# Adafruit_Ethernet_FeatherWing.net
KiCad netlist of a schematic drawn in EAGLE
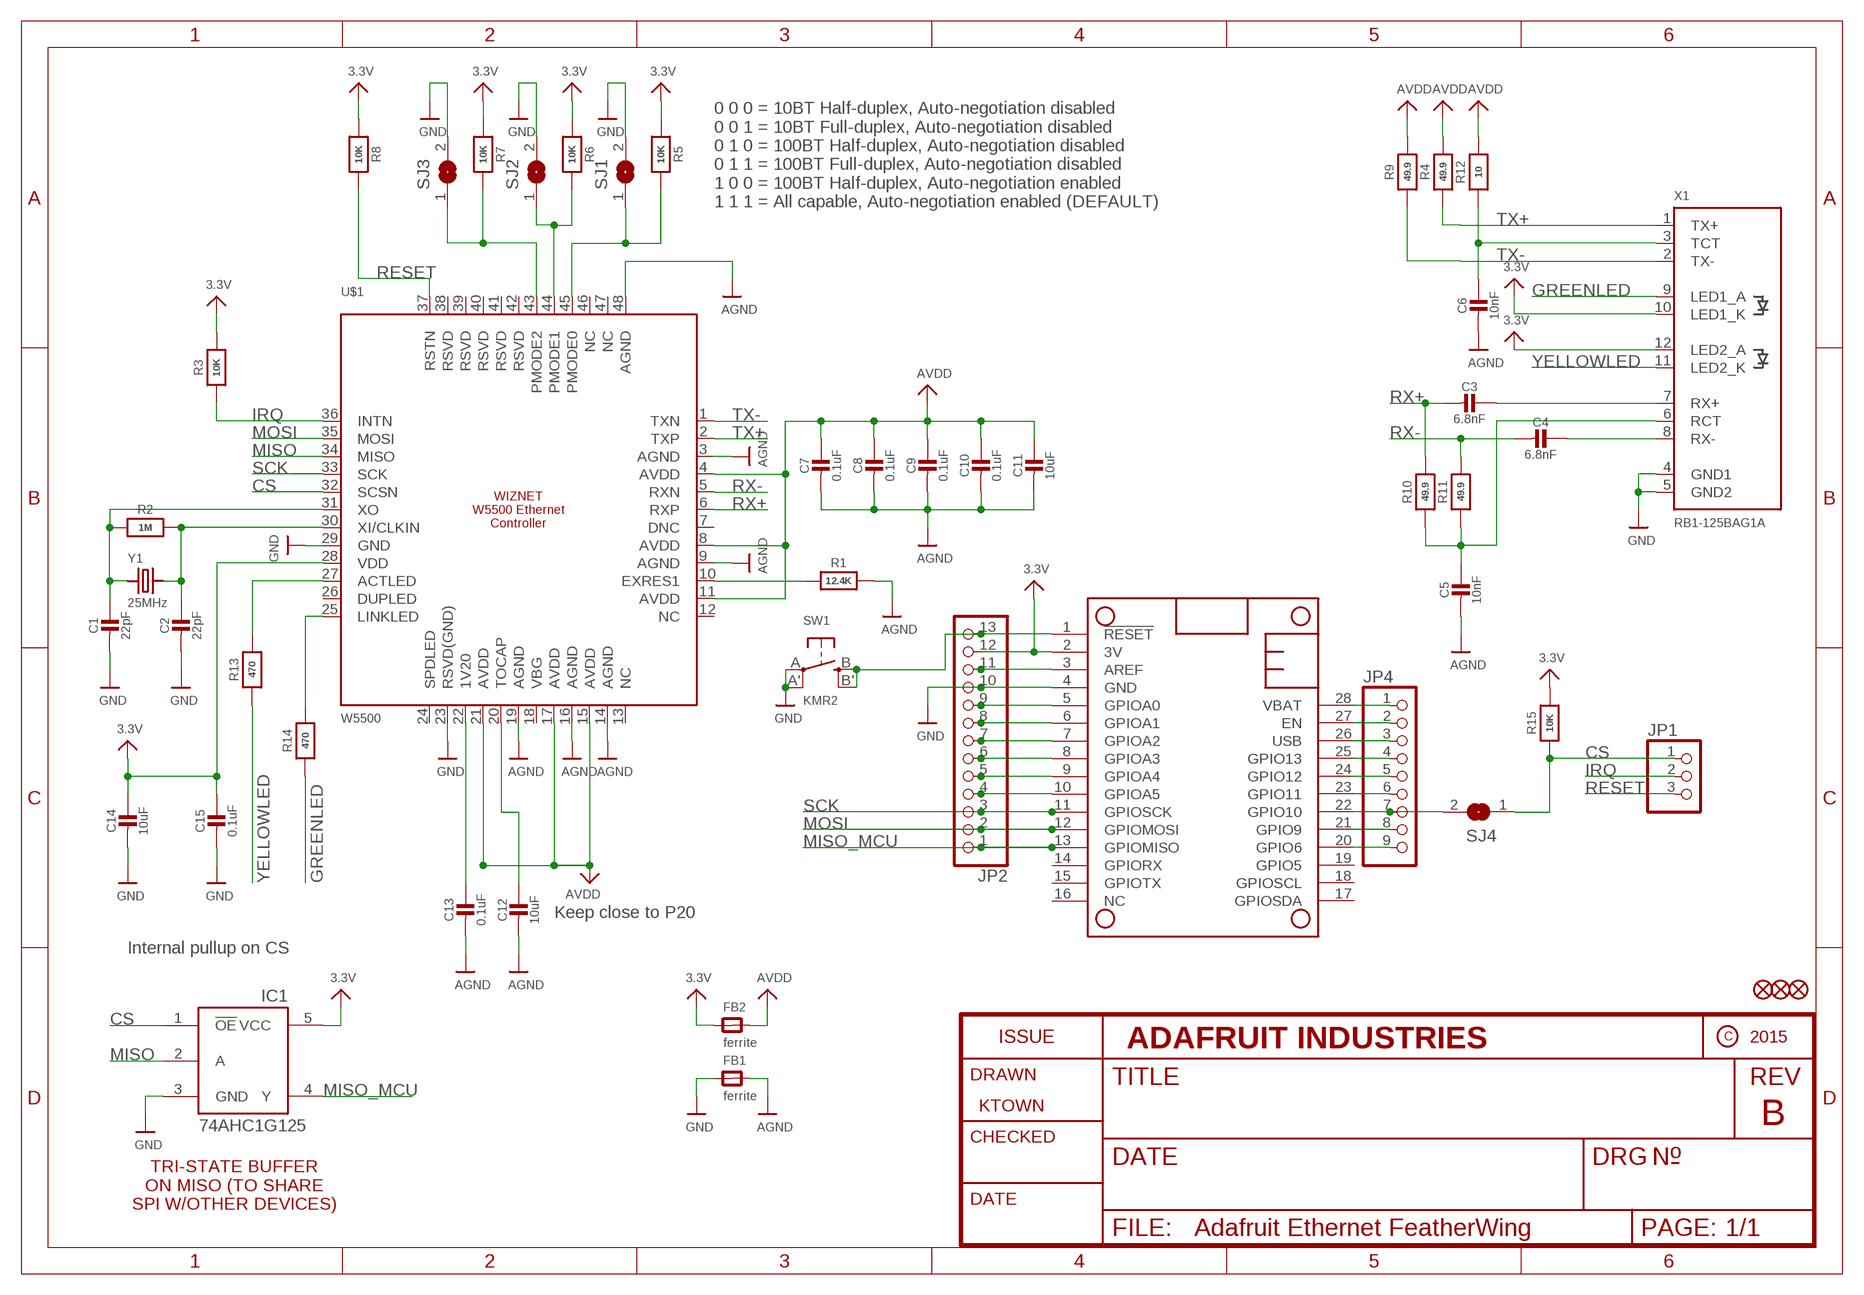
[diagram p0: schematic, sheet 1]

(export (version "E")
  (design (tool "Eeschema 10.0.6"))
  (components
    (comp (ref "C1")
      (value "22pF")
      (footprint "eagle-import:0603-NO")
      (libsource (lib "eagle-import") (part "CAP_CERAMIC0603_NO"))
    )
    (comp (ref "C2")
      (value "22pF")
      (footprint "eagle-import:0603-NO")
      (libsource (lib "eagle-import") (part "CAP_CERAMIC0603_NO"))
    )
    (comp (ref "C3")
      (value "6.8nF")
      (footprint "eagle-import:0603-NO")
      (libsource (lib "eagle-import") (part "CAP_CERAMIC0603_NO"))
    )
    (comp (ref "C4")
      (value "6.8nF")
      (footprint "eagle-import:0603-NO")
      (libsource (lib "eagle-import") (part "CAP_CERAMIC0603_NO"))
    )
    (comp (ref "C5")
      (value "10nF")
      (footprint "eagle-import:0603-NO")
      (libsource (lib "eagle-import") (part "CAP_CERAMIC0603_NO"))
    )
    (comp (ref "C6")
      (value "10nF")
      (footprint "eagle-import:0603-NO")
      (libsource (lib "eagle-import") (part "CAP_CERAMIC0603_NO"))
    )
    (comp (ref "C7")
      (value "0.1uF")
      (footprint "eagle-import:0603-NO")
      (libsource (lib "eagle-import") (part "CAP_CERAMIC0603_NO"))
    )
    (comp (ref "C8")
      (value "0.1uF")
      (footprint "eagle-import:0603-NO")
      (libsource (lib "eagle-import") (part "CAP_CERAMIC0603_NO"))
    )
    (comp (ref "C9")
      (value "0.1uF")
      (footprint "eagle-import:0603-NO")
      (libsource (lib "eagle-import") (part "CAP_CERAMIC0603_NO"))
    )
    (comp (ref "C10")
      (value "0.1uF")
      (footprint "eagle-import:0603-NO")
      (libsource (lib "eagle-import") (part "CAP_CERAMIC0603_NO"))
    )
    (comp (ref "C11")
      (value "10uF")
      (footprint "eagle-import:0805-NO")
      (libsource (lib "eagle-import") (part "CAP_CERAMIC0805-NOOUTLINE"))
    )
    (comp (ref "C12")
      (value "10uF")
      (footprint "eagle-import:0805-NO")
      (libsource (lib "eagle-import") (part "CAP_CERAMIC0805-NOOUTLINE"))
    )
    (comp (ref "C13")
      (value "0.1uF")
      (footprint "eagle-import:0603-NO")
      (libsource (lib "eagle-import") (part "CAP_CERAMIC0603_NO"))
    )
    (comp (ref "C14")
      (value "10uF")
      (footprint "eagle-import:0805-NO")
      (libsource (lib "eagle-import") (part "CAP_CERAMIC0805-NOOUTLINE"))
    )
    (comp (ref "C15")
      (value "0.1uF")
      (footprint "eagle-import:0603-NO")
      (libsource (lib "eagle-import") (part "CAP_CERAMIC0603_NO"))
    )
    (comp (ref "FB1")
      (value "ferrite")
      (footprint "eagle-import:0805-NO")
      (libsource (lib "eagle-import") (part "FERRITE-0805NO"))
    )
    (comp (ref "FB2")
      (value "ferrite")
      (footprint "eagle-import:0805-NO")
      (libsource (lib "eagle-import") (part "FERRITE-0805NO"))
    )
    (comp (ref "FID1")
      (value "FIDUCIAL\"\"")
      (footprint "eagle-import:FIDUCIAL_1MM")
      (libsource (lib "eagle-import") (part "FIDUCIAL{dblquote}{dblquote}"))
    )
    (comp (ref "FID2")
      (value "FIDUCIAL\"\"")
      (footprint "eagle-import:FIDUCIAL_1MM")
      (libsource (lib "eagle-import") (part "FIDUCIAL{dblquote}{dblquote}"))
    )
    (comp (ref "FID3")
      (value "FIDUCIAL\"\"")
      (footprint "eagle-import:FIDUCIAL_1MM")
      (libsource (lib "eagle-import") (part "FIDUCIAL{dblquote}{dblquote}"))
    )
    (comp (ref "IC1")
      (value "74AHC1G125")
      (footprint "eagle-import:SOT23-5L")
      (libsource (lib "eagle-import") (part "74AHC1G125"))
    )
    (comp (ref "JP1")
      (value "HEADER-1X376MIL")
      (footprint "eagle-import:1X03_ROUND_76")
      (libsource (lib "eagle-import") (part "HEADER-1X376MIL"))
    )
    (comp (ref "JP2")
      (value "HEADER-1X13")
      (footprint "eagle-import:1X13_ROUND_70")
      (libsource (lib "eagle-import") (part "HEADER-1X13"))
    )
    (comp (ref "JP4")
      (value "HEADER-1X970MIL")
      (footprint "eagle-import:1X09_ROUND_70")
      (libsource (lib "eagle-import") (part "HEADER-1X970MIL"))
    )
    (comp (ref "MS1")
      (value "FEATHERWING_NODIM")
      (footprint "eagle-import:FEATHERWING_NODIM")
      (libsource (lib "eagle-import") (part "FEATHERWING_NODIM"))
    )
    (comp (ref "R1")
      (value "12.4K")
      (footprint "eagle-import:0603-NO")
      (libsource (lib "eagle-import") (part "RESISTOR_0603_NOOUT"))
    )
    (comp (ref "R2")
      (value "1M")
      (footprint "eagle-import:0603-NO")
      (libsource (lib "eagle-import") (part "RESISTOR_0603_NOOUT"))
    )
    (comp (ref "R3")
      (value "10K")
      (footprint "eagle-import:0603-NO")
      (libsource (lib "eagle-import") (part "RESISTOR_0603_NOOUT"))
    )
    (comp (ref "R4")
      (value "49.9")
      (footprint "eagle-import:0603-NO")
      (libsource (lib "eagle-import") (part "RESISTOR_0603_NOOUT"))
    )
    (comp (ref "R5")
      (value "10K")
      (footprint "eagle-import:0603-NO")
      (libsource (lib "eagle-import") (part "RESISTOR_0603_NOOUT"))
    )
    (comp (ref "R6")
      (value "10K")
      (footprint "eagle-import:0603-NO")
      (libsource (lib "eagle-import") (part "RESISTOR_0603_NOOUT"))
    )
    (comp (ref "R7")
      (value "10K")
      (footprint "eagle-import:0603-NO")
      (libsource (lib "eagle-import") (part "RESISTOR_0603_NOOUT"))
    )
    (comp (ref "R8")
      (value "10K")
      (footprint "eagle-import:0603-NO")
      (libsource (lib "eagle-import") (part "RESISTOR_0603_NOOUT"))
    )
    (comp (ref "R9")
      (value "49.9")
      (footprint "eagle-import:0603-NO")
      (libsource (lib "eagle-import") (part "RESISTOR_0603_NOOUT"))
    )
    (comp (ref "R10")
      (value "49.9")
      (footprint "eagle-import:0603-NO")
      (libsource (lib "eagle-import") (part "RESISTOR_0603_NOOUT"))
    )
    (comp (ref "R11")
      (value "49.9")
      (footprint "eagle-import:0603-NO")
      (libsource (lib "eagle-import") (part "RESISTOR_0603_NOOUT"))
    )
    (comp (ref "R12")
      (value "10")
      (footprint "eagle-import:0603-NO")
      (libsource (lib "eagle-import") (part "RESISTOR_0603_NOOUT"))
    )
    (comp (ref "R13")
      (value "470")
      (footprint "eagle-import:0603-NO")
      (libsource (lib "eagle-import") (part "RESISTOR_0603_NOOUT"))
    )
    (comp (ref "R14")
      (value "470")
      (footprint "eagle-import:0603-NO")
      (libsource (lib "eagle-import") (part "RESISTOR_0603_NOOUT"))
    )
    (comp (ref "R15")
      (value "10K")
      (footprint "eagle-import:0603-NO")
      (libsource (lib "eagle-import") (part "RESISTOR_0603_NOOUT"))
    )
    (comp (ref "SJ1")
      (value "SOLDERJUMPERREFLOW_NOPASTE")
      (footprint "eagle-import:SOLDERJUMPER_REFLOW_NOPASTE")
      (libsource (lib "eagle-import") (part "SOLDERJUMPERREFLOW_NOPASTE"))
    )
    (comp (ref "SJ2")
      (value "SOLDERJUMPERREFLOW_NOPASTE")
      (footprint "eagle-import:SOLDERJUMPER_REFLOW_NOPASTE")
      (libsource (lib "eagle-import") (part "SOLDERJUMPERREFLOW_NOPASTE"))
    )
    (comp (ref "SJ3")
      (value "SOLDERJUMPERREFLOW_NOPASTE")
      (footprint "eagle-import:SOLDERJUMPER_REFLOW_NOPASTE")
      (libsource (lib "eagle-import") (part "SOLDERJUMPERREFLOW_NOPASTE"))
    )
    (comp (ref "SJ4")
      (value "SOLDERJUMPERCLOSED")
      (footprint "eagle-import:SOLDERJUMPER_CLOSEDWIRE")
      (libsource (lib "eagle-import") (part "SOLDERJUMPERCLOSED"))
    )
    (comp (ref "SW1")
      (value "KMR2")
      (footprint "eagle-import:BTN_KMR2_4.6X2.8")
      (libsource (lib "eagle-import") (part "SWITCH_TACT_SMT4.6X2.8"))
    )
    (comp (ref "U$1")
      (value "W5500")
      (footprint "eagle-import:LQFP48")
      (libsource (lib "eagle-import") (part "WIZNET_W5500"))
    )
    (comp (ref "X1")
      (value "RB1-125BAG1A")
      (footprint "eagle-import:RJ45_PULSEJACK")
      (libsource (lib "eagle-import") (part "RJ45J0026D21BNL"))
    )
    (comp (ref "Y1")
      (value "25MHz")
      (footprint "eagle-import:CRYSTAL_3.2X2.5")
      (libsource (lib "eagle-import") (part "CRYSTAL3.2X2.5"))
    )
  )
  (nets
    (net (code "1") (name "/CS") (class "Default")
      (node (ref "IC1") (pin "1") (pinfunction "~{OE}_1") (pintype "input"))
      (node (ref "JP1") (pin "1") (pinfunction "1_1") (pintype "passive"))
      (node (ref "R15") (pin "1") (pinfunction "1_1") (pintype "passive"))
      (node (ref "SJ4") (pin "1") (pinfunction "1_1") (pintype "passive"))
      (node (ref "U$1") (pin "32") (pinfunction "SCSN_32") (pintype "input"))
    )
    (net (code "2") (name "/GREENLED") (class "Default")
      (node (ref "R14") (pin "1") (pinfunction "1_1") (pintype "passive"))
      (node (ref "X1") (pin "9") (pinfunction "LED1_A_9") (pintype "bidirectional"))
    )
    (net (code "3") (name "/IRQ") (class "Default")
      (node (ref "JP1") (pin "2") (pinfunction "2_2") (pintype "passive"))
      (node (ref "R3") (pin "1") (pinfunction "1_1") (pintype "passive"))
      (node (ref "U$1") (pin "36") (pinfunction "INTN_36") (pintype "output"))
    )
    (net (code "4") (name "/MISO") (class "Default")
      (node (ref "IC1") (pin "2") (pinfunction "A_2") (pintype "input"))
      (node (ref "U$1") (pin "34") (pinfunction "MISO_34") (pintype "output"))
    )
    (net (code "5") (name "/MISO_MCU") (class "Default")
      (node (ref "IC1") (pin "4") (pinfunction "Y_4") (pintype "output"))
      (node (ref "JP2") (pin "1") (pinfunction "1_1") (pintype "passive"))
      (node (ref "MS1") (pin "13") (pinfunction "GPIOMISO_13") (pintype "bidirectional"))
    )
    (net (code "6") (name "/MOSI") (class "Default")
      (node (ref "JP2") (pin "2") (pinfunction "2_2") (pintype "passive"))
      (node (ref "MS1") (pin "12") (pinfunction "GPIOMOSI_12") (pintype "bidirectional"))
      (node (ref "U$1") (pin "35") (pinfunction "MOSI_35") (pintype "input"))
    )
    (net (code "7") (name "/RESET") (class "Default")
      (node (ref "JP1") (pin "3") (pinfunction "3_3") (pintype "passive"))
      (node (ref "R8") (pin "2") (pinfunction "2_2") (pintype "passive"))
      (node (ref "U$1") (pin "37") (pinfunction "RSTN_37") (pintype "input"))
    )
    (net (code "8") (name "/RX+") (class "Default")
      (node (ref "C3") (pin "2") (pinfunction "2_2") (pintype "passive"))
      (node (ref "R10") (pin "2") (pinfunction "2_2") (pintype "passive"))
      (node (ref "U$1") (pin "6") (pinfunction "RXP_6") (pintype "input"))
    )
    (net (code "9") (name "/RX-") (class "Default")
      (node (ref "C4") (pin "2") (pinfunction "2_2") (pintype "passive"))
      (node (ref "R11") (pin "2") (pinfunction "2_2") (pintype "passive"))
      (node (ref "U$1") (pin "5") (pinfunction "RXN_5") (pintype "input"))
    )
    (net (code "10") (name "/SCK") (class "Default")
      (node (ref "JP2") (pin "3") (pinfunction "3_3") (pintype "passive"))
      (node (ref "MS1") (pin "11") (pinfunction "GPIOSCK_11") (pintype "bidirectional"))
      (node (ref "U$1") (pin "33") (pinfunction "SCK_33") (pintype "input"))
    )
    (net (code "11") (name "/TX+") (class "Default")
      (node (ref "R4") (pin "1") (pinfunction "1_1") (pintype "passive"))
      (node (ref "U$1") (pin "2") (pinfunction "TXP_2") (pintype "output"))
      (node (ref "X1") (pin "1") (pinfunction "TX+_1") (pintype "bidirectional"))
    )
    (net (code "12") (name "/TX-") (class "Default")
      (node (ref "R9") (pin "1") (pinfunction "1_1") (pintype "passive"))
      (node (ref "U$1") (pin "1") (pinfunction "TXN_1") (pintype "output"))
      (node (ref "X1") (pin "2") (pinfunction "TX-_2") (pintype "bidirectional"))
    )
    (net (code "13") (name "/YELLOWLED") (class "Default")
      (node (ref "R13") (pin "1") (pinfunction "1_1") (pintype "passive"))
      (node (ref "X1") (pin "11") (pinfunction "LED2_K_11") (pintype "bidirectional"))
    )
    (net (code "14") (name "3.3V") (class "Default")
      (node (ref "C14") (pin "1") (pinfunction "1_1") (pintype "passive"))
      (node (ref "C15") (pin "1") (pinfunction "1_1") (pintype "passive"))
      (node (ref "FB2") (pin "1") (pinfunction "P$1_1") (pintype "passive"))
      (node (ref "IC1") (pin "5") (pinfunction "VCC_5") (pintype "power_in"))
      (node (ref "JP2") (pin "12") (pinfunction "12_12") (pintype "passive"))
      (node (ref "MS1") (pin "2") (pinfunction "3V_2") (pintype "power_in"))
      (node (ref "R15") (pin "2") (pinfunction "2_2") (pintype "passive"))
      (node (ref "R3") (pin "2") (pinfunction "2_2") (pintype "passive"))
      (node (ref "R5") (pin "1") (pinfunction "1_1") (pintype "passive"))
      (node (ref "R6") (pin "1") (pinfunction "1_1") (pintype "passive"))
      (node (ref "R7") (pin "1") (pinfunction "1_1") (pintype "passive"))
      (node (ref "R8") (pin "1") (pinfunction "1_1") (pintype "passive"))
      (node (ref "U$1") (pin "28") (pinfunction "VDD_28") (pintype "power_in"))
      (node (ref "X1") (pin "10") (pinfunction "LED1_K_10") (pintype "bidirectional"))
      (node (ref "X1") (pin "12") (pinfunction "LED2_A_12") (pintype "bidirectional"))
    )
    (net (code "15") (name "AGND") (class "Default")
      (node (ref "C10") (pin "2") (pinfunction "2_2") (pintype "passive"))
      (node (ref "C11") (pin "2") (pinfunction "2_2") (pintype "passive"))
      (node (ref "C12") (pin "2") (pinfunction "2_2") (pintype "passive"))
      (node (ref "C13") (pin "2") (pinfunction "2_2") (pintype "passive"))
      (node (ref "C5") (pin "2") (pinfunction "2_2") (pintype "passive"))
      (node (ref "C6") (pin "2") (pinfunction "2_2") (pintype "passive"))
      (node (ref "C7") (pin "2") (pinfunction "2_2") (pintype "passive"))
      (node (ref "C8") (pin "2") (pinfunction "2_2") (pintype "passive"))
      (node (ref "C9") (pin "2") (pinfunction "2_2") (pintype "passive"))
      (node (ref "FB1") (pin "2") (pinfunction "P$2_2") (pintype "passive"))
      (node (ref "R1") (pin "2") (pinfunction "2_2") (pintype "passive"))
      (node (ref "U$1") (pin "14") (pinfunction "AGND_14") (pintype "power_in"))
      (node (ref "U$1") (pin "16") (pinfunction "AGND_16") (pintype "power_in"))
      (node (ref "U$1") (pin "19") (pinfunction "AGND_19") (pintype "power_in"))
      (node (ref "U$1") (pin "3") (pinfunction "AGND_3") (pintype "power_in"))
      (node (ref "U$1") (pin "48") (pinfunction "AGND_48") (pintype "power_in"))
      (node (ref "U$1") (pin "9") (pinfunction "AGND_9") (pintype "power_in"))
    )
    (net (code "16") (name "AVDD") (class "Default")
      (node (ref "C10") (pin "1") (pinfunction "1_1") (pintype "passive"))
      (node (ref "C11") (pin "1") (pinfunction "1_1") (pintype "passive"))
      (node (ref "C7") (pin "1") (pinfunction "1_1") (pintype "passive"))
      (node (ref "C8") (pin "1") (pinfunction "1_1") (pintype "passive"))
      (node (ref "C9") (pin "1") (pinfunction "1_1") (pintype "passive"))
      (node (ref "FB2") (pin "2") (pinfunction "P$2_2") (pintype "passive"))
      (node (ref "R12") (pin "2") (pinfunction "2_2") (pintype "passive"))
      (node (ref "R4") (pin "2") (pinfunction "2_2") (pintype "passive"))
      (node (ref "R9") (pin "2") (pinfunction "2_2") (pintype "passive"))
      (node (ref "U$1") (pin "11") (pinfunction "AVDD_11") (pintype "power_in"))
      (node (ref "U$1") (pin "15") (pinfunction "AVDD_15") (pintype "power_in"))
      (node (ref "U$1") (pin "17") (pinfunction "AVDD_17") (pintype "power_in"))
      (node (ref "U$1") (pin "21") (pinfunction "AVDD_21") (pintype "power_in"))
      (node (ref "U$1") (pin "4") (pinfunction "AVDD_4") (pintype "power_in"))
      (node (ref "U$1") (pin "8") (pinfunction "AVDD_8") (pintype "power_in"))
    )
    (net (code "17") (name "GND") (class "Default")
      (node (ref "C1") (pin "2") (pinfunction "2_2") (pintype "passive"))
      (node (ref "C14") (pin "2") (pinfunction "2_2") (pintype "passive"))
      (node (ref "C15") (pin "2") (pinfunction "2_2") (pintype "passive"))
      (node (ref "C2") (pin "2") (pinfunction "2_2") (pintype "passive"))
      (node (ref "FB1") (pin "1") (pinfunction "P$1_1") (pintype "passive"))
      (node (ref "IC1") (pin "3") (pinfunction "GND_3") (pintype "power_in"))
      (node (ref "JP2") (pin "10") (pinfunction "10_10") (pintype "passive"))
      (node (ref "MS1") (pin "4") (pinfunction "GND_4") (pintype "power_in"))
      (node (ref "SJ1") (pin "2") (pinfunction "2_2") (pintype "passive"))
      (node (ref "SJ2") (pin "2") (pinfunction "2_2") (pintype "passive"))
      (node (ref "SJ3") (pin "2") (pinfunction "2_2") (pintype "passive"))
      (node (ref "SW1") (pin "A") (pinfunction "P_A") (pintype "passive"))
      (node (ref "SW1") (pin "A'") (pinfunction "P1_A'") (pintype "passive"))
      (node (ref "U$1") (pin "23") (pinfunction "RSVD(GND)_23") (pintype "input"))
      (node (ref "U$1") (pin "29") (pinfunction "GND_29") (pintype "power_in"))
      (node (ref "X1") (pin "4") (pinfunction "GND1_4") (pintype "bidirectional"))
      (node (ref "X1") (pin "5") (pinfunction "GND2_5") (pintype "bidirectional"))
    )
    (net (code "18") (name "Net-(MS1-AREF)") (class "Default")
      (node (ref "JP2") (pin "11") (pinfunction "11_11") (pintype "passive"))
      (node (ref "MS1") (pin "3") (pinfunction "AREF_3") (pintype "passive"))
    )
    (net (code "19") (name "Net-(MS1-EN)") (class "Default")
      (node (ref "JP4") (pin "2") (pinfunction "2_2") (pintype "passive"))
      (node (ref "MS1") (pin "27") (pinfunction "EN_27") (pintype "passive"))
    )
    (net (code "20") (name "Net-(MS1-GPIO6)") (class "Default")
      (node (ref "JP4") (pin "9") (pinfunction "9_9") (pintype "passive"))
      (node (ref "MS1") (pin "20") (pinfunction "GPIO6_20") (pintype "bidirectional"))
    )
    (net (code "21") (name "Net-(MS1-GPIO9)") (class "Default")
      (node (ref "JP4") (pin "8") (pinfunction "8_8") (pintype "passive"))
      (node (ref "MS1") (pin "21") (pinfunction "GPIO9_21") (pintype "bidirectional"))
    )
    (net (code "22") (name "Net-(MS1-GPIO10)") (class "Default")
      (node (ref "JP4") (pin "7") (pinfunction "7_7") (pintype "passive"))
      (node (ref "MS1") (pin "22") (pinfunction "GPIO10_22") (pintype "bidirectional"))
      (node (ref "SJ4") (pin "2") (pinfunction "2_2") (pintype "passive"))
    )
    (net (code "23") (name "Net-(MS1-GPIO11)") (class "Default")
      (node (ref "JP4") (pin "6") (pinfunction "6_6") (pintype "passive"))
      (node (ref "MS1") (pin "23") (pinfunction "GPIO11_23") (pintype "bidirectional"))
    )
    (net (code "24") (name "Net-(MS1-GPIO12)") (class "Default")
      (node (ref "JP4") (pin "5") (pinfunction "5_5") (pintype "passive"))
      (node (ref "MS1") (pin "24") (pinfunction "GPIO12_24") (pintype "bidirectional"))
    )
    (net (code "25") (name "Net-(MS1-GPIO13)") (class "Default")
      (node (ref "JP4") (pin "4") (pinfunction "4_4") (pintype "passive"))
      (node (ref "MS1") (pin "25") (pinfunction "GPIO13_25") (pintype "bidirectional"))
    )
    (net (code "26") (name "Net-(MS1-GPIOA0)") (class "Default")
      (node (ref "JP2") (pin "9") (pinfunction "9_9") (pintype "passive"))
      (node (ref "MS1") (pin "5") (pinfunction "GPIOA0_5") (pintype "bidirectional"))
    )
    (net (code "27") (name "Net-(MS1-GPIOA1)") (class "Default")
      (node (ref "JP2") (pin "8") (pinfunction "8_8") (pintype "passive"))
      (node (ref "MS1") (pin "6") (pinfunction "GPIOA1_6") (pintype "bidirectional"))
    )
    (net (code "28") (name "Net-(MS1-GPIOA2)") (class "Default")
      (node (ref "JP2") (pin "7") (pinfunction "7_7") (pintype "passive"))
      (node (ref "MS1") (pin "7") (pinfunction "GPIOA2_7") (pintype "bidirectional"))
    )
    (net (code "29") (name "Net-(MS1-GPIOA3)") (class "Default")
      (node (ref "JP2") (pin "6") (pinfunction "6_6") (pintype "passive"))
      (node (ref "MS1") (pin "8") (pinfunction "GPIOA3_8") (pintype "bidirectional"))
    )
    (net (code "30") (name "Net-(MS1-GPIOA4)") (class "Default")
      (node (ref "JP2") (pin "5") (pinfunction "5_5") (pintype "passive"))
      (node (ref "MS1") (pin "9") (pinfunction "GPIOA4_9") (pintype "bidirectional"))
    )
    (net (code "31") (name "Net-(MS1-GPIOA5)") (class "Default")
      (node (ref "JP2") (pin "4") (pinfunction "4_4") (pintype "passive"))
      (node (ref "MS1") (pin "10") (pinfunction "GPIOA5_10") (pintype "bidirectional"))
    )
    (net (code "32") (name "Net-(MS1-USB)") (class "Default")
      (node (ref "JP4") (pin "3") (pinfunction "3_3") (pintype "passive"))
      (node (ref "MS1") (pin "26") (pinfunction "USB_26") (pintype "power_in"))
    )
    (net (code "33") (name "Net-(MS1-VBAT)") (class "Default")
      (node (ref "JP4") (pin "1") (pinfunction "1_1") (pintype "passive"))
      (node (ref "MS1") (pin "28") (pinfunction "VBAT_28") (pintype "power_in"))
    )
    (net (code "34") (name "Net-(MS1-~{RESET})") (class "Default")
      (node (ref "JP2") (pin "13") (pinfunction "13_13") (pintype "passive"))
      (node (ref "MS1") (pin "1") (pinfunction "~{RESET}_1") (pintype "input"))
      (node (ref "SW1") (pin "B") (pinfunction "S_B") (pintype "passive"))
      (node (ref "SW1") (pin "B'") (pinfunction "S1_B'") (pintype "passive"))
    )
    (net (code "35") (name "Net-(U$1-1V20)") (class "Default")
      (node (ref "C13") (pin "1") (pinfunction "1_1") (pintype "passive"))
      (node (ref "U$1") (pin "22") (pinfunction "1V20_22") (pintype "power_in"))
    )
    (net (code "36") (name "Net-(U$1-ACTLED)") (class "Default")
      (node (ref "R13") (pin "2") (pinfunction "2_2") (pintype "passive"))
      (node (ref "U$1") (pin "27") (pinfunction "ACTLED_27") (pintype "output"))
    )
    (net (code "37") (name "Net-(U$1-EXRES1)") (class "Default")
      (node (ref "R1") (pin "1") (pinfunction "1_1") (pintype "passive"))
      (node (ref "U$1") (pin "10") (pinfunction "EXRES1_10") (pintype "bidirectional"))
    )
    (net (code "38") (name "Net-(U$1-LINKLED)") (class "Default")
      (node (ref "R14") (pin "2") (pinfunction "2_2") (pintype "passive"))
      (node (ref "U$1") (pin "25") (pinfunction "LINKLED_25") (pintype "output"))
    )
    (net (code "39") (name "Net-(U$1-PMODE0)") (class "Default")
      (node (ref "R5") (pin "2") (pinfunction "2_2") (pintype "passive"))
      (node (ref "SJ1") (pin "1") (pinfunction "1_1") (pintype "passive"))
      (node (ref "U$1") (pin "45") (pinfunction "PMODE0_45") (pintype "input"))
    )
    (net (code "40") (name "Net-(U$1-PMODE1)") (class "Default")
      (node (ref "R6") (pin "2") (pinfunction "2_2") (pintype "passive"))
      (node (ref "SJ2") (pin "1") (pinfunction "1_1") (pintype "passive"))
      (node (ref "U$1") (pin "44") (pinfunction "PMODE1_44") (pintype "input"))
    )
    (net (code "41") (name "Net-(U$1-PMODE2)") (class "Default")
      (node (ref "R7") (pin "2") (pinfunction "2_2") (pintype "passive"))
      (node (ref "SJ3") (pin "1") (pinfunction "1_1") (pintype "passive"))
      (node (ref "U$1") (pin "43") (pinfunction "PMODE2_43") (pintype "input"))
    )
    (net (code "42") (name "Net-(U$1-TOCAP)") (class "Default")
      (node (ref "C12") (pin "1") (pinfunction "1_1") (pintype "passive"))
      (node (ref "U$1") (pin "20") (pinfunction "TOCAP_20") (pintype "output"))
    )
    (net (code "43") (name "Net-(U$1-XI{slash}CLKIN)") (class "Default")
      (node (ref "C2") (pin "1") (pinfunction "1_1") (pintype "passive"))
      (node (ref "R2") (pin "2") (pinfunction "2_2") (pintype "passive"))
      (node (ref "U$1") (pin "30") (pinfunction "XI/CLKIN_30") (pintype "input"))
      (node (ref "Y1") (pin "2") (pinfunction "2_2") (pintype "passive"))
    )
    (net (code "44") (name "Net-(U$1-XO)") (class "Default")
      (node (ref "C1") (pin "1") (pinfunction "1_1") (pintype "passive"))
      (node (ref "R2") (pin "1") (pinfunction "1_1") (pintype "passive"))
      (node (ref "U$1") (pin "31") (pinfunction "XO_31") (pintype "output"))
      (node (ref "Y1") (pin "1") (pinfunction "1_1") (pintype "passive"))
    )
    (net (code "45") (name "Net-(X1-RCT)") (class "Default")
      (node (ref "C5") (pin "1") (pinfunction "1_1") (pintype "passive"))
      (node (ref "R10") (pin "1") (pinfunction "1_1") (pintype "passive"))
      (node (ref "R11") (pin "1") (pinfunction "1_1") (pintype "passive"))
      (node (ref "X1") (pin "6") (pinfunction "RCT_6") (pintype "bidirectional"))
    )
    (net (code "46") (name "Net-(X1-RX+)") (class "Default")
      (node (ref "C3") (pin "1") (pinfunction "1_1") (pintype "passive"))
      (node (ref "X1") (pin "7") (pinfunction "RX+_7") (pintype "bidirectional"))
    )
    (net (code "47") (name "Net-(X1-RX-)") (class "Default")
      (node (ref "C4") (pin "1") (pinfunction "1_1") (pintype "passive"))
      (node (ref "X1") (pin "8") (pinfunction "RX-_8") (pintype "bidirectional"))
    )
    (net (code "48") (name "Net-(X1-TCT)") (class "Default")
      (node (ref "C6") (pin "1") (pinfunction "1_1") (pintype "passive"))
      (node (ref "R12") (pin "1") (pinfunction "1_1") (pintype "passive"))
      (node (ref "X1") (pin "3") (pinfunction "TCT_3") (pintype "bidirectional"))
    )
    (net (code "49") (name "unconnected-(MS1-GPIO5-Pad19)") (class "Default")
      (node (ref "MS1") (pin "19") (pinfunction "GPIO5_19") (pintype "bidirectional"))
    )
    (net (code "50") (name "unconnected-(MS1-GPIORX-Pad14)") (class "Default")
      (node (ref "MS1") (pin "14") (pinfunction "GPIORX_14") (pintype "bidirectional"))
    )
    (net (code "51") (name "unconnected-(MS1-GPIOSCL-Pad18)") (class "Default")
      (node (ref "MS1") (pin "18") (pinfunction "GPIOSCL_18") (pintype "bidirectional"))
    )
    (net (code "52") (name "unconnected-(MS1-GPIOSDA-Pad17)") (class "Default")
      (node (ref "MS1") (pin "17") (pinfunction "GPIOSDA_17") (pintype "bidirectional"))
    )
    (net (code "53") (name "unconnected-(MS1-GPIOTX-Pad15)") (class "Default")
      (node (ref "MS1") (pin "15") (pinfunction "GPIOTX_15") (pintype "bidirectional"))
    )
    (net (code "54") (name "unconnected-(MS1-NC-Pad16)") (class "Default")
      (node (ref "MS1") (pin "16") (pinfunction "NC_16") (pintype "passive"))
    )
    (net (code "55") (name "unconnected-(U$1-DNC-Pad7)") (class "Default")
      (node (ref "U$1") (pin "7") (pinfunction "DNC_7") (pintype "no_connect"))
    )
    (net (code "56") (name "unconnected-(U$1-DUPLED-Pad26)") (class "Default")
      (node (ref "U$1") (pin "26") (pinfunction "DUPLED_26") (pintype "output"))
    )
    (net (code "57") (name "unconnected-(U$1-NC-Pad12)") (class "Default")
      (node (ref "U$1") (pin "12") (pinfunction "NC_12") (pintype "no_connect"))
    )
    (net (code "58") (name "unconnected-(U$1-NC-Pad13)") (class "Default")
      (node (ref "U$1") (pin "13") (pinfunction "NC_13") (pintype "no_connect"))
    )
    (net (code "59") (name "unconnected-(U$1-NC-Pad46)") (class "Default")
      (node (ref "U$1") (pin "46") (pinfunction "NC_46") (pintype "no_connect"))
    )
    (net (code "60") (name "unconnected-(U$1-NC-Pad47)") (class "Default")
      (node (ref "U$1") (pin "47") (pinfunction "NC_47") (pintype "no_connect"))
    )
    (net (code "61") (name "unconnected-(U$1-RSVD-Pad38)") (class "Default")
      (node (ref "U$1") (pin "38") (pinfunction "RSVD_38") (pintype "no_connect"))
    )
    (net (code "62") (name "unconnected-(U$1-RSVD-Pad39)") (class "Default")
      (node (ref "U$1") (pin "39") (pinfunction "RSVD_39") (pintype "no_connect"))
    )
    (net (code "63") (name "unconnected-(U$1-RSVD-Pad40)") (class "Default")
      (node (ref "U$1") (pin "40") (pinfunction "RSVD_40") (pintype "no_connect"))
    )
    (net (code "64") (name "unconnected-(U$1-RSVD-Pad41)") (class "Default")
      (node (ref "U$1") (pin "41") (pinfunction "RSVD_41") (pintype "no_connect"))
    )
    (net (code "65") (name "unconnected-(U$1-RSVD-Pad42)") (class "Default")
      (node (ref "U$1") (pin "42") (pinfunction "RSVD_42") (pintype "no_connect"))
    )
    (net (code "66") (name "unconnected-(U$1-SPDLED-Pad24)") (class "Default")
      (node (ref "U$1") (pin "24") (pinfunction "SPDLED_24") (pintype "output"))
    )
    (net (code "67") (name "unconnected-(U$1-VBG-Pad18)") (class "Default")
      (node (ref "U$1") (pin "18") (pinfunction "VBG_18") (pintype "output"))
    )
  )
)
